# ledB_sch.net
KiCad netlist of a schematic drawn in EAGLE
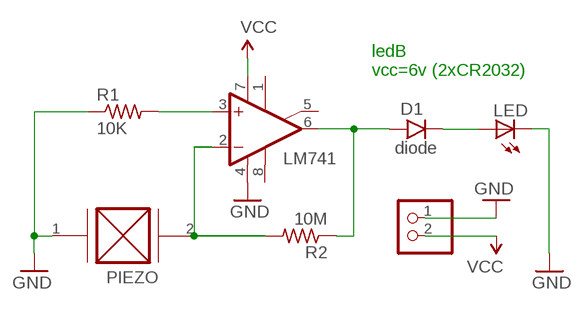
[diagram p0: schematic, sheet 1]

(export (version "E")
  (design (tool "Eeschema 10.0.6"))
  (components
    (comp (ref "D1")
      (value "diode")
      (footprint "eagle-import:DO35-3")
      (libsource (lib "eagle-import") (part "1N4148-3"))
    )
    (comp (ref "JP1")
      (value "6V+")
      (footprint "eagle-import:1X02_OVAL")
      (libsource (lib "eagle-import") (part "HEADER-1X2"))
    )
    (comp (ref "LED")
      (value "LED5MM")
      (footprint "eagle-import:LED5MM")
      (libsource (lib "eagle-import") (part "LED5MM"))
    )
    (comp (ref "OPAMP")
      (value "LM741")
      (footprint "eagle-import:DIL08")
      (libsource (lib "eagle-import") (part "741PLM"))
    )
    (comp (ref "PIEZO")
      (value "PIEZO")
      (footprint "eagle-import:1X02_PEIZO")
      (libsource (lib "eagle-import") (part "PIEZO"))
    )
    (comp (ref "R1")
      (value "10K")
      (footprint "eagle-import:0204_7")
      (libsource (lib "eagle-import") (part "R-US_0204/7"))
    )
    (comp (ref "R2")
      (value "10M")
      (footprint "eagle-import:0204_7")
      (libsource (lib "eagle-import") (part "R-US_0204/7"))
    )
  )
  (nets
    (net (code "1") (name "GND") (class "Default")
      (node (ref "JP1") (pin "1") (pinfunction "1_1") (pintype "passive"))
      (node (ref "LED") (pin "K") (pinfunction "C_K") (pintype "passive"))
      (node (ref "OPAMP") (pin "4") (pinfunction "V-_4") (pintype "power_in"))
      (node (ref "PIEZO") (pin "1") (pinfunction "GND_1") (pintype "passive"))
      (node (ref "R1") (pin "1") (pinfunction "1_1") (pintype "passive"))
    )
    (net (code "2") (name "Net-(D1-PadC)") (class "Default")
      (node (ref "D1") (pin "C") (pinfunction "C_C") (pintype "passive"))
      (node (ref "LED") (pin "A") (pinfunction "A_A") (pintype "passive"))
    )
    (net (code "3") (name "Net-(OPAMP-+IN)") (class "Default")
      (node (ref "OPAMP") (pin "3") (pinfunction "+IN_3") (pintype "input"))
      (node (ref "R1") (pin "2") (pinfunction "2_2") (pintype "passive"))
    )
    (net (code "4") (name "Net-(OPAMP--IN)") (class "Default")
      (node (ref "OPAMP") (pin "2") (pinfunction "-IN_2") (pintype "input"))
      (node (ref "PIEZO") (pin "2") (pinfunction "OUT+_2") (pintype "passive"))
      (node (ref "R2") (pin "2") (pinfunction "2_2") (pintype "passive"))
    )
    (net (code "5") (name "Net-(OPAMP-OUT)") (class "Default")
      (node (ref "D1") (pin "A") (pinfunction "A_A") (pintype "passive"))
      (node (ref "OPAMP") (pin "6") (pinfunction "OUT_6") (pintype "output"))
      (node (ref "R2") (pin "1") (pinfunction "1_1") (pintype "passive"))
    )
    (net (code "6") (name "VCC") (class "Default")
      (node (ref "JP1") (pin "2") (pinfunction "2_2") (pintype "passive"))
      (node (ref "OPAMP") (pin "7") (pinfunction "V+_7") (pintype "power_in"))
    )
    (net (code "7") (name "unconnected-(OPAMP-ON1-Pad1)") (class "Default")
      (node (ref "OPAMP") (pin "1") (pinfunction "ON1_1") (pintype "passive"))
    )
    (net (code "8") (name "unconnected-(OPAMP-ON2-Pad5)") (class "Default")
      (node (ref "OPAMP") (pin "5") (pinfunction "ON2_5") (pintype "passive"))
    )
    (net (code "9") (name "unconnected-(OPAMP-OPT-Pad8)") (class "Default")
      (node (ref "OPAMP") (pin "8") (pinfunction "OPT_8") (pintype "passive"))
    )
  )
)
